# SN74AHC1G09.net
KiCad netlist of a schematic drawn in EAGLE
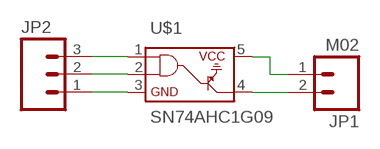
[diagram p0: schematic, sheet 1]

(export (version "E")
  (design (tool "Eeschema 10.0.6"))
  (components
    (comp (ref "JP1")
      (value "M02")
      (footprint "eagle-import:1X02")
      (libsource (lib "eagle-import") (part "M02"))
    )
    (comp (ref "JP2")
      (value "M03")
      (footprint "eagle-import:1X03")
      (libsource (lib "eagle-import") (part "M03"))
    )
    (comp (ref "U$1")
      (value "SN74AHC1G09")
      (footprint "eagle-import:SOT-23-5")
      (libsource (lib "eagle-import") (part "SN74AHC1G09"))
    )
  )
  (nets
    (net (code "1") (name "Net-(JP1-Pad1)") (class "Default")
      (node (ref "JP1") (pin "1") (pinfunction "1_1") (pintype "passive"))
      (node (ref "U$1") (pin "5") (pinfunction "5_5") (pintype "passive"))
    )
    (net (code "2") (name "Net-(JP1-Pad2)") (class "Default")
      (node (ref "JP1") (pin "2") (pinfunction "2_2") (pintype "passive"))
      (node (ref "U$1") (pin "4") (pinfunction "4_4") (pintype "passive"))
    )
    (net (code "3") (name "Net-(JP2-Pad1)") (class "Default")
      (node (ref "JP2") (pin "1") (pinfunction "1_1") (pintype "passive"))
      (node (ref "U$1") (pin "3") (pinfunction "3_3") (pintype "passive"))
    )
    (net (code "4") (name "Net-(JP2-Pad2)") (class "Default")
      (node (ref "JP2") (pin "2") (pinfunction "2_2") (pintype "passive"))
      (node (ref "U$1") (pin "2") (pinfunction "2_2") (pintype "passive"))
    )
    (net (code "5") (name "Net-(JP2-Pad3)") (class "Default")
      (node (ref "JP2") (pin "3") (pinfunction "3_3") (pintype "passive"))
      (node (ref "U$1") (pin "1") (pinfunction "1_1") (pintype "passive"))
    )
  )
)
